# MiniCoil_-_Cap_Board.net
KiCad netlist of a schematic drawn in Altium Designer
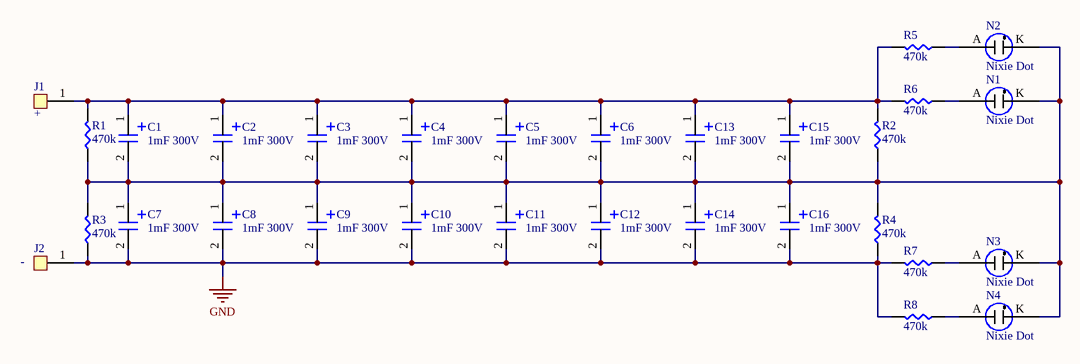
[diagram p0: MiniCoil - Cap Board.SchDoc]

(export (version "E")
  (design (tool "Eeschema 10.0.6"))
  (components
    (comp (ref "C1")
      (value "1mF 300V")
      (footprint "ELKO 35x50x10")
      (libsource (lib "stdLib") (part "Cap Polar"))
    )
    (comp (ref "C2")
      (value "1mF 300V")
      (footprint "ELKO 35x50x10")
      (libsource (lib "stdLib") (part "Cap Polar"))
    )
    (comp (ref "C3")
      (value "1mF 300V")
      (footprint "ELKO 35x50x10")
      (libsource (lib "stdLib") (part "Cap Polar"))
    )
    (comp (ref "C4")
      (value "1mF 300V")
      (footprint "ELKO 35x50x10")
      (libsource (lib "stdLib") (part "Cap Polar"))
    )
    (comp (ref "C5")
      (value "1mF 300V")
      (footprint "ELKO 35x50x10")
      (libsource (lib "stdLib") (part "Cap Polar"))
    )
    (comp (ref "C6")
      (value "1mF 300V")
      (footprint "ELKO 35x50x10")
      (libsource (lib "stdLib") (part "Cap Polar"))
    )
    (comp (ref "C7")
      (value "1mF 300V")
      (footprint "ELKO 35x50x10")
      (libsource (lib "stdLib") (part "Cap Polar"))
    )
    (comp (ref "C8")
      (value "1mF 300V")
      (footprint "ELKO 35x50x10")
      (libsource (lib "stdLib") (part "Cap Polar"))
    )
    (comp (ref "C9")
      (value "1mF 300V")
      (footprint "ELKO 35x50x10")
      (libsource (lib "stdLib") (part "Cap Polar"))
    )
    (comp (ref "C10")
      (value "1mF 300V")
      (footprint "ELKO 35x50x10")
      (libsource (lib "stdLib") (part "Cap Polar"))
    )
    (comp (ref "C11")
      (value "1mF 300V")
      (footprint "ELKO 35x50x10")
      (libsource (lib "stdLib") (part "Cap Polar"))
    )
    (comp (ref "C12")
      (value "1mF 300V")
      (footprint "ELKO 35x50x10")
      (libsource (lib "stdLib") (part "Cap Polar"))
    )
    (comp (ref "C13")
      (value "1mF 300V")
      (footprint "ELKO 35x50x10")
      (libsource (lib "stdLib") (part "Cap Polar"))
    )
    (comp (ref "C14")
      (value "1mF 300V")
      (footprint "ELKO 35x50x10")
      (libsource (lib "stdLib") (part "Cap Polar"))
    )
    (comp (ref "C15")
      (value "1mF 300V")
      (footprint "ELKO 35x50x10")
      (libsource (lib "stdLib") (part "Cap Polar"))
    )
    (comp (ref "C16")
      (value "1mF 300V")
      (footprint "ELKO 35x50x10")
      (libsource (lib "stdLib") (part "Cap Polar"))
    )
    (comp (ref "J1")
      (value "+")
      (footprint "575-8 Banana Jack")
      (libsource (lib "stdLib") (part "Binding Post 1 Pin"))
    )
    (comp (ref "J2")
      (value "-")
      (footprint "575-8 Banana Jack")
      (libsource (lib "stdLib") (part "Binding Post 1 Pin"))
    )
    (comp (ref "N1")
      (value "Nixie Dot")
      (footprint "INS-1")
      (description "Neon dot indicator")
      (libsource (lib "stdLib") (part "Nixie Dot"))
    )
    (comp (ref "N2")
      (value "Nixie Dot")
      (footprint "INS-1")
      (description "Neon dot indicator")
      (libsource (lib "stdLib") (part "Nixie Dot"))
    )
    (comp (ref "N3")
      (value "Nixie Dot")
      (footprint "INS-1")
      (description "Neon dot indicator")
      (libsource (lib "stdLib") (part "Nixie Dot"))
    )
    (comp (ref "N4")
      (value "Nixie Dot")
      (footprint "INS-1")
      (description "Neon dot indicator")
      (libsource (lib "stdLib") (part "Nixie Dot"))
    )
    (comp (ref "R1") (value "470k") (footprint "SQM-03 3W") (libsource (lib "stdLib") (part "Resistor")))
    (comp (ref "R2") (value "470k") (footprint "SQM-03 3W") (libsource (lib "stdLib") (part "Resistor")))
    (comp (ref "R3") (value "470k") (footprint "SQM-03 3W") (libsource (lib "stdLib") (part "Resistor")))
    (comp (ref "R4") (value "470k") (footprint "SQM-03 3W") (libsource (lib "stdLib") (part "Resistor")))
    (comp (ref "R5") (value "470k") (footprint "0207 THT") (libsource (lib "stdLib") (part "Resistor")))
    (comp (ref "R6") (value "470k") (footprint "0207 THT") (libsource (lib "stdLib") (part "Resistor")))
    (comp (ref "R7") (value "470k") (footprint "0207 THT") (libsource (lib "stdLib") (part "Resistor")))
    (comp (ref "R8") (value "470k") (footprint "0207 THT") (libsource (lib "stdLib") (part "Resistor")))
  )
  (nets
    (net (code "1") (name "GND") (class "Default")
      (node (ref "C10") (pin "2") (pintype "passive"))
      (node (ref "C11") (pin "2") (pintype "passive"))
      (node (ref "C12") (pin "2") (pintype "passive"))
      (node (ref "C14") (pin "2") (pintype "passive"))
      (node (ref "C16") (pin "2") (pintype "passive"))
      (node (ref "C7") (pin "2") (pintype "passive"))
      (node (ref "C8") (pin "2") (pintype "passive"))
      (node (ref "C9") (pin "2") (pintype "passive"))
      (node (ref "J2") (pin "1") (pinfunction "O_1") (pintype "passive"))
      (node (ref "R3") (pin "1") (pinfunction "1_1") (pintype "passive"))
      (node (ref "R4") (pin "1") (pinfunction "1_1") (pintype "passive"))
      (node (ref "R7") (pin "2") (pinfunction "2_2") (pintype "passive"))
      (node (ref "R8") (pin "2") (pinfunction "2_2") (pintype "passive"))
    )
    (net (code "2") (name "Net-(C1-Pad2)") (class "Default")
      (node (ref "C1") (pin "2") (pintype "passive"))
      (node (ref "C10") (pin "1") (pintype "passive"))
      (node (ref "C11") (pin "1") (pintype "passive"))
      (node (ref "C12") (pin "1") (pintype "passive"))
      (node (ref "C13") (pin "2") (pintype "passive"))
      (node (ref "C14") (pin "1") (pintype "passive"))
      (node (ref "C15") (pin "2") (pintype "passive"))
      (node (ref "C16") (pin "1") (pintype "passive"))
      (node (ref "C2") (pin "2") (pintype "passive"))
      (node (ref "C3") (pin "2") (pintype "passive"))
      (node (ref "C4") (pin "2") (pintype "passive"))
      (node (ref "C5") (pin "2") (pintype "passive"))
      (node (ref "C6") (pin "2") (pintype "passive"))
      (node (ref "C7") (pin "1") (pintype "passive"))
      (node (ref "C8") (pin "1") (pintype "passive"))
      (node (ref "C9") (pin "1") (pintype "passive"))
      (node (ref "N1") (pin "K") (pinfunction "K_K") (pintype "power_in"))
      (node (ref "N2") (pin "K") (pinfunction "K_K") (pintype "power_in"))
      (node (ref "N3") (pin "K") (pinfunction "K_K") (pintype "power_in"))
      (node (ref "N4") (pin "K") (pinfunction "K_K") (pintype "power_in"))
      (node (ref "R1") (pin "1") (pinfunction "1_1") (pintype "passive"))
      (node (ref "R2") (pin "1") (pinfunction "1_1") (pintype "passive"))
      (node (ref "R3") (pin "2") (pinfunction "2_2") (pintype "passive"))
      (node (ref "R4") (pin "2") (pinfunction "2_2") (pintype "passive"))
    )
    (net (code "3") (name "Net-(J1-O)") (class "Default")
      (node (ref "C1") (pin "1") (pintype "passive"))
      (node (ref "C13") (pin "1") (pintype "passive"))
      (node (ref "C15") (pin "1") (pintype "passive"))
      (node (ref "C2") (pin "1") (pintype "passive"))
      (node (ref "C3") (pin "1") (pintype "passive"))
      (node (ref "C4") (pin "1") (pintype "passive"))
      (node (ref "C5") (pin "1") (pintype "passive"))
      (node (ref "C6") (pin "1") (pintype "passive"))
      (node (ref "J1") (pin "1") (pinfunction "O_1") (pintype "passive"))
      (node (ref "R1") (pin "2") (pinfunction "2_2") (pintype "passive"))
      (node (ref "R2") (pin "2") (pinfunction "2_2") (pintype "passive"))
      (node (ref "R5") (pin "2") (pinfunction "2_2") (pintype "passive"))
      (node (ref "R6") (pin "2") (pinfunction "2_2") (pintype "passive"))
    )
    (net (code "4") (name "Net-(N1-PadA)") (class "Default")
      (node (ref "N1") (pin "A") (pinfunction "A_A") (pintype "power_in"))
      (node (ref "R6") (pin "1") (pinfunction "1_1") (pintype "passive"))
    )
    (net (code "5") (name "Net-(N2-PadA)") (class "Default")
      (node (ref "N2") (pin "A") (pinfunction "A_A") (pintype "power_in"))
      (node (ref "R5") (pin "1") (pinfunction "1_1") (pintype "passive"))
    )
    (net (code "6") (name "Net-(N3-PadA)") (class "Default")
      (node (ref "N3") (pin "A") (pinfunction "A_A") (pintype "power_in"))
      (node (ref "R7") (pin "1") (pinfunction "1_1") (pintype "passive"))
    )
    (net (code "7") (name "Net-(N4-PadA)") (class "Default")
      (node (ref "N4") (pin "A") (pinfunction "A_A") (pintype "power_in"))
      (node (ref "R8") (pin "1") (pinfunction "1_1") (pintype "passive"))
    )
  )
)
